# thopi_0_1.net
KiCad netlist of a schematic drawn in EAGLE
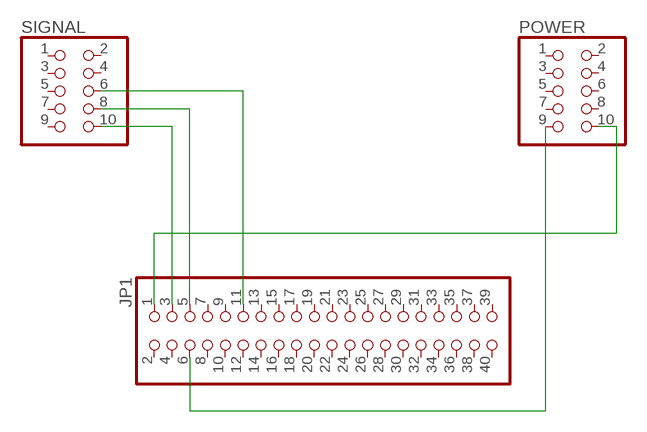
[diagram p0: schematic, sheet 1]

(export (version "E")
  (design (tool "Eeschema 10.0.6"))
  (components
    (comp (ref "JP1")
      (value "PINHD-2X20")
      (footprint "eagle-import:2X20")
      (libsource (lib "eagle-import") (part "PINHD-2X20"))
    )
    (comp (ref "POWER")
      (value "PINHD-2X5")
      (footprint "eagle-import:2X05")
      (libsource (lib "eagle-import") (part "PINHD-2X5"))
    )
    (comp (ref "SIGNAL")
      (value "PINHD-2X5")
      (footprint "eagle-import:2X05")
      (libsource (lib "eagle-import") (part "PINHD-2X5"))
    )
  )
  (nets
    (net (code "1") (name "Net-(JP1-Pad1)") (class "Default")
      (node (ref "JP1") (pin "1") (pinfunction "1_1") (pintype "passive"))
      (node (ref "POWER") (pin "10") (pinfunction "10_10") (pintype "passive"))
    )
    (net (code "2") (name "Net-(JP1-Pad3)") (class "Default")
      (node (ref "JP1") (pin "3") (pinfunction "3_3") (pintype "passive"))
      (node (ref "SIGNAL") (pin "10") (pinfunction "10_10") (pintype "passive"))
    )
    (net (code "3") (name "Net-(JP1-Pad5)") (class "Default")
      (node (ref "JP1") (pin "5") (pinfunction "5_5") (pintype "passive"))
      (node (ref "SIGNAL") (pin "8") (pinfunction "8_8") (pintype "passive"))
    )
    (net (code "4") (name "Net-(JP1-Pad6)") (class "Default")
      (node (ref "JP1") (pin "6") (pinfunction "6_6") (pintype "passive"))
      (node (ref "POWER") (pin "9") (pinfunction "9_9") (pintype "passive"))
    )
    (net (code "5") (name "Net-(JP1-Pad11)") (class "Default")
      (node (ref "JP1") (pin "11") (pinfunction "11_11") (pintype "passive"))
      (node (ref "SIGNAL") (pin "6") (pinfunction "6_6") (pintype "passive"))
    )
    (net (code "6") (name "unconnected-(JP1-Pad2)") (class "Default")
      (node (ref "JP1") (pin "2") (pinfunction "2_2") (pintype "passive"))
    )
    (net (code "7") (name "unconnected-(JP1-Pad4)") (class "Default")
      (node (ref "JP1") (pin "4") (pinfunction "4_4") (pintype "passive"))
    )
    (net (code "8") (name "unconnected-(JP1-Pad7)") (class "Default")
      (node (ref "JP1") (pin "7") (pinfunction "7_7") (pintype "passive"))
    )
    (net (code "9") (name "unconnected-(JP1-Pad8)") (class "Default")
      (node (ref "JP1") (pin "8") (pinfunction "8_8") (pintype "passive"))
    )
    (net (code "10") (name "unconnected-(JP1-Pad9)") (class "Default")
      (node (ref "JP1") (pin "9") (pinfunction "9_9") (pintype "passive"))
    )
    (net (code "11") (name "unconnected-(JP1-Pad10)") (class "Default")
      (node (ref "JP1") (pin "10") (pinfunction "10_10") (pintype "passive"))
    )
    (net (code "12") (name "unconnected-(JP1-Pad12)") (class "Default")
      (node (ref "JP1") (pin "12") (pinfunction "12_12") (pintype "passive"))
    )
    (net (code "13") (name "unconnected-(JP1-Pad13)") (class "Default")
      (node (ref "JP1") (pin "13") (pinfunction "13_13") (pintype "passive"))
    )
    (net (code "14") (name "unconnected-(JP1-Pad14)") (class "Default")
      (node (ref "JP1") (pin "14") (pinfunction "14_14") (pintype "passive"))
    )
    (net (code "15") (name "unconnected-(JP1-Pad15)") (class "Default")
      (node (ref "JP1") (pin "15") (pinfunction "15_15") (pintype "passive"))
    )
    (net (code "16") (name "unconnected-(JP1-Pad16)") (class "Default")
      (node (ref "JP1") (pin "16") (pinfunction "16_16") (pintype "passive"))
    )
    (net (code "17") (name "unconnected-(JP1-Pad17)") (class "Default")
      (node (ref "JP1") (pin "17") (pinfunction "17_17") (pintype "passive"))
    )
    (net (code "18") (name "unconnected-(JP1-Pad18)") (class "Default")
      (node (ref "JP1") (pin "18") (pinfunction "18_18") (pintype "passive"))
    )
    (net (code "19") (name "unconnected-(JP1-Pad19)") (class "Default")
      (node (ref "JP1") (pin "19") (pinfunction "19_19") (pintype "passive"))
    )
    (net (code "20") (name "unconnected-(JP1-Pad20)") (class "Default")
      (node (ref "JP1") (pin "20") (pinfunction "20_20") (pintype "passive"))
    )
    (net (code "21") (name "unconnected-(JP1-Pad21)") (class "Default")
      (node (ref "JP1") (pin "21") (pinfunction "21_21") (pintype "passive"))
    )
    (net (code "22") (name "unconnected-(JP1-Pad22)") (class "Default")
      (node (ref "JP1") (pin "22") (pinfunction "22_22") (pintype "passive"))
    )
    (net (code "23") (name "unconnected-(JP1-Pad23)") (class "Default")
      (node (ref "JP1") (pin "23") (pinfunction "23_23") (pintype "passive"))
    )
    (net (code "24") (name "unconnected-(JP1-Pad24)") (class "Default")
      (node (ref "JP1") (pin "24") (pinfunction "24_24") (pintype "passive"))
    )
    (net (code "25") (name "unconnected-(JP1-Pad25)") (class "Default")
      (node (ref "JP1") (pin "25") (pinfunction "25_25") (pintype "passive"))
    )
    (net (code "26") (name "unconnected-(JP1-Pad26)") (class "Default")
      (node (ref "JP1") (pin "26") (pinfunction "26_26") (pintype "passive"))
    )
    (net (code "27") (name "unconnected-(JP1-Pad27)") (class "Default")
      (node (ref "JP1") (pin "27") (pinfunction "27_27") (pintype "passive"))
    )
    (net (code "28") (name "unconnected-(JP1-Pad28)") (class "Default")
      (node (ref "JP1") (pin "28") (pinfunction "28_28") (pintype "passive"))
    )
    (net (code "29") (name "unconnected-(JP1-Pad29)") (class "Default")
      (node (ref "JP1") (pin "29") (pinfunction "29_29") (pintype "passive"))
    )
    (net (code "30") (name "unconnected-(JP1-Pad30)") (class "Default")
      (node (ref "JP1") (pin "30") (pinfunction "30_30") (pintype "passive"))
    )
    (net (code "31") (name "unconnected-(JP1-Pad31)") (class "Default")
      (node (ref "JP1") (pin "31") (pinfunction "31_31") (pintype "passive"))
    )
    (net (code "32") (name "unconnected-(JP1-Pad32)") (class "Default")
      (node (ref "JP1") (pin "32") (pinfunction "32_32") (pintype "passive"))
    )
    (net (code "33") (name "unconnected-(JP1-Pad33)") (class "Default")
      (node (ref "JP1") (pin "33") (pinfunction "33_33") (pintype "passive"))
    )
    (net (code "34") (name "unconnected-(JP1-Pad34)") (class "Default")
      (node (ref "JP1") (pin "34") (pinfunction "34_34") (pintype "passive"))
    )
    (net (code "35") (name "unconnected-(JP1-Pad35)") (class "Default")
      (node (ref "JP1") (pin "35") (pinfunction "35_35") (pintype "passive"))
    )
    (net (code "36") (name "unconnected-(JP1-Pad36)") (class "Default")
      (node (ref "JP1") (pin "36") (pinfunction "36_36") (pintype "passive"))
    )
    (net (code "37") (name "unconnected-(JP1-Pad37)") (class "Default")
      (node (ref "JP1") (pin "37") (pinfunction "37_37") (pintype "passive"))
    )
    (net (code "38") (name "unconnected-(JP1-Pad38)") (class "Default")
      (node (ref "JP1") (pin "38") (pinfunction "38_38") (pintype "passive"))
    )
    (net (code "39") (name "unconnected-(JP1-Pad39)") (class "Default")
      (node (ref "JP1") (pin "39") (pinfunction "39_39") (pintype "passive"))
    )
    (net (code "40") (name "unconnected-(JP1-Pad40)") (class "Default")
      (node (ref "JP1") (pin "40") (pinfunction "40_40") (pintype "passive"))
    )
    (net (code "41") (name "unconnected-(POWER-Pad1)") (class "Default")
      (node (ref "POWER") (pin "1") (pinfunction "1_1") (pintype "passive"))
    )
    (net (code "42") (name "unconnected-(POWER-Pad2)") (class "Default")
      (node (ref "POWER") (pin "2") (pinfunction "2_2") (pintype "passive"))
    )
    (net (code "43") (name "unconnected-(POWER-Pad3)") (class "Default")
      (node (ref "POWER") (pin "3") (pinfunction "3_3") (pintype "passive"))
    )
    (net (code "44") (name "unconnected-(POWER-Pad4)") (class "Default")
      (node (ref "POWER") (pin "4") (pinfunction "4_4") (pintype "passive"))
    )
    (net (code "45") (name "unconnected-(POWER-Pad5)") (class "Default")
      (node (ref "POWER") (pin "5") (pinfunction "5_5") (pintype "passive"))
    )
    (net (code "46") (name "unconnected-(POWER-Pad6)") (class "Default")
      (node (ref "POWER") (pin "6") (pinfunction "6_6") (pintype "passive"))
    )
    (net (code "47") (name "unconnected-(POWER-Pad7)") (class "Default")
      (node (ref "POWER") (pin "7") (pinfunction "7_7") (pintype "passive"))
    )
    (net (code "48") (name "unconnected-(POWER-Pad8)") (class "Default")
      (node (ref "POWER") (pin "8") (pinfunction "8_8") (pintype "passive"))
    )
    (net (code "49") (name "unconnected-(SIGNAL-Pad1)") (class "Default")
      (node (ref "SIGNAL") (pin "1") (pinfunction "1_1") (pintype "passive"))
    )
    (net (code "50") (name "unconnected-(SIGNAL-Pad2)") (class "Default")
      (node (ref "SIGNAL") (pin "2") (pinfunction "2_2") (pintype "passive"))
    )
    (net (code "51") (name "unconnected-(SIGNAL-Pad3)") (class "Default")
      (node (ref "SIGNAL") (pin "3") (pinfunction "3_3") (pintype "passive"))
    )
    (net (code "52") (name "unconnected-(SIGNAL-Pad4)") (class "Default")
      (node (ref "SIGNAL") (pin "4") (pinfunction "4_4") (pintype "passive"))
    )
    (net (code "53") (name "unconnected-(SIGNAL-Pad5)") (class "Default")
      (node (ref "SIGNAL") (pin "5") (pinfunction "5_5") (pintype "passive"))
    )
    (net (code "54") (name "unconnected-(SIGNAL-Pad7)") (class "Default")
      (node (ref "SIGNAL") (pin "7") (pinfunction "7_7") (pintype "passive"))
    )
    (net (code "55") (name "unconnected-(SIGNAL-Pad9)") (class "Default")
      (node (ref "SIGNAL") (pin "9") (pinfunction "9_9") (pintype "passive"))
    )
  )
)
